# Sheet2.net
KiCad netlist of a schematic drawn in Altium Designer
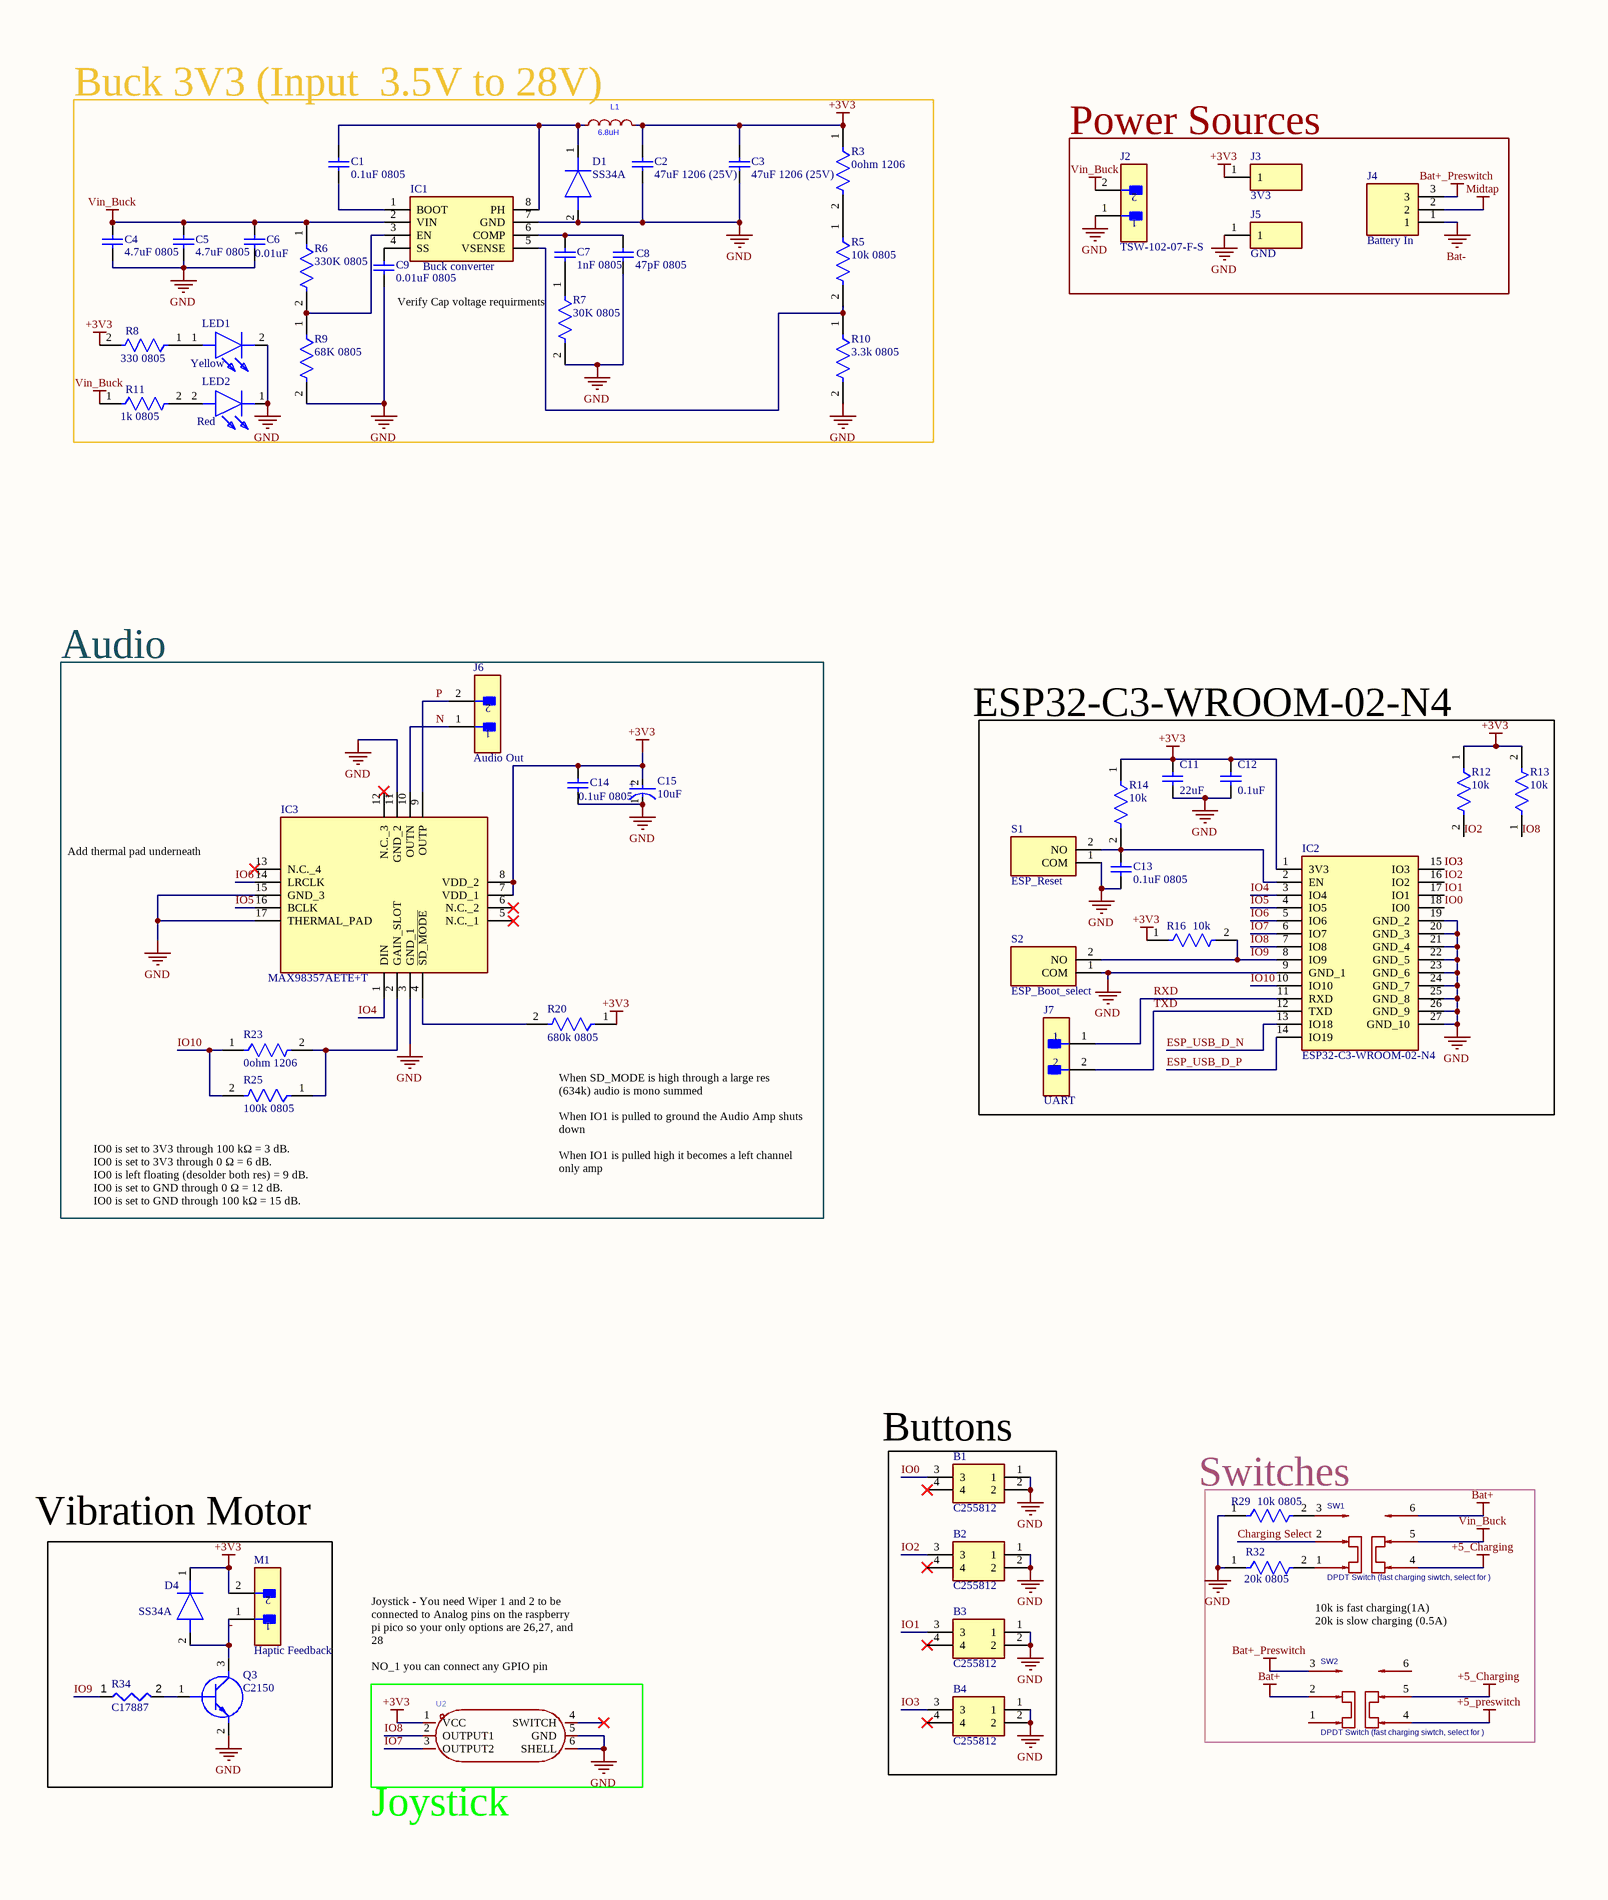
[diagram p0: Sheet2.SchDoc, left]
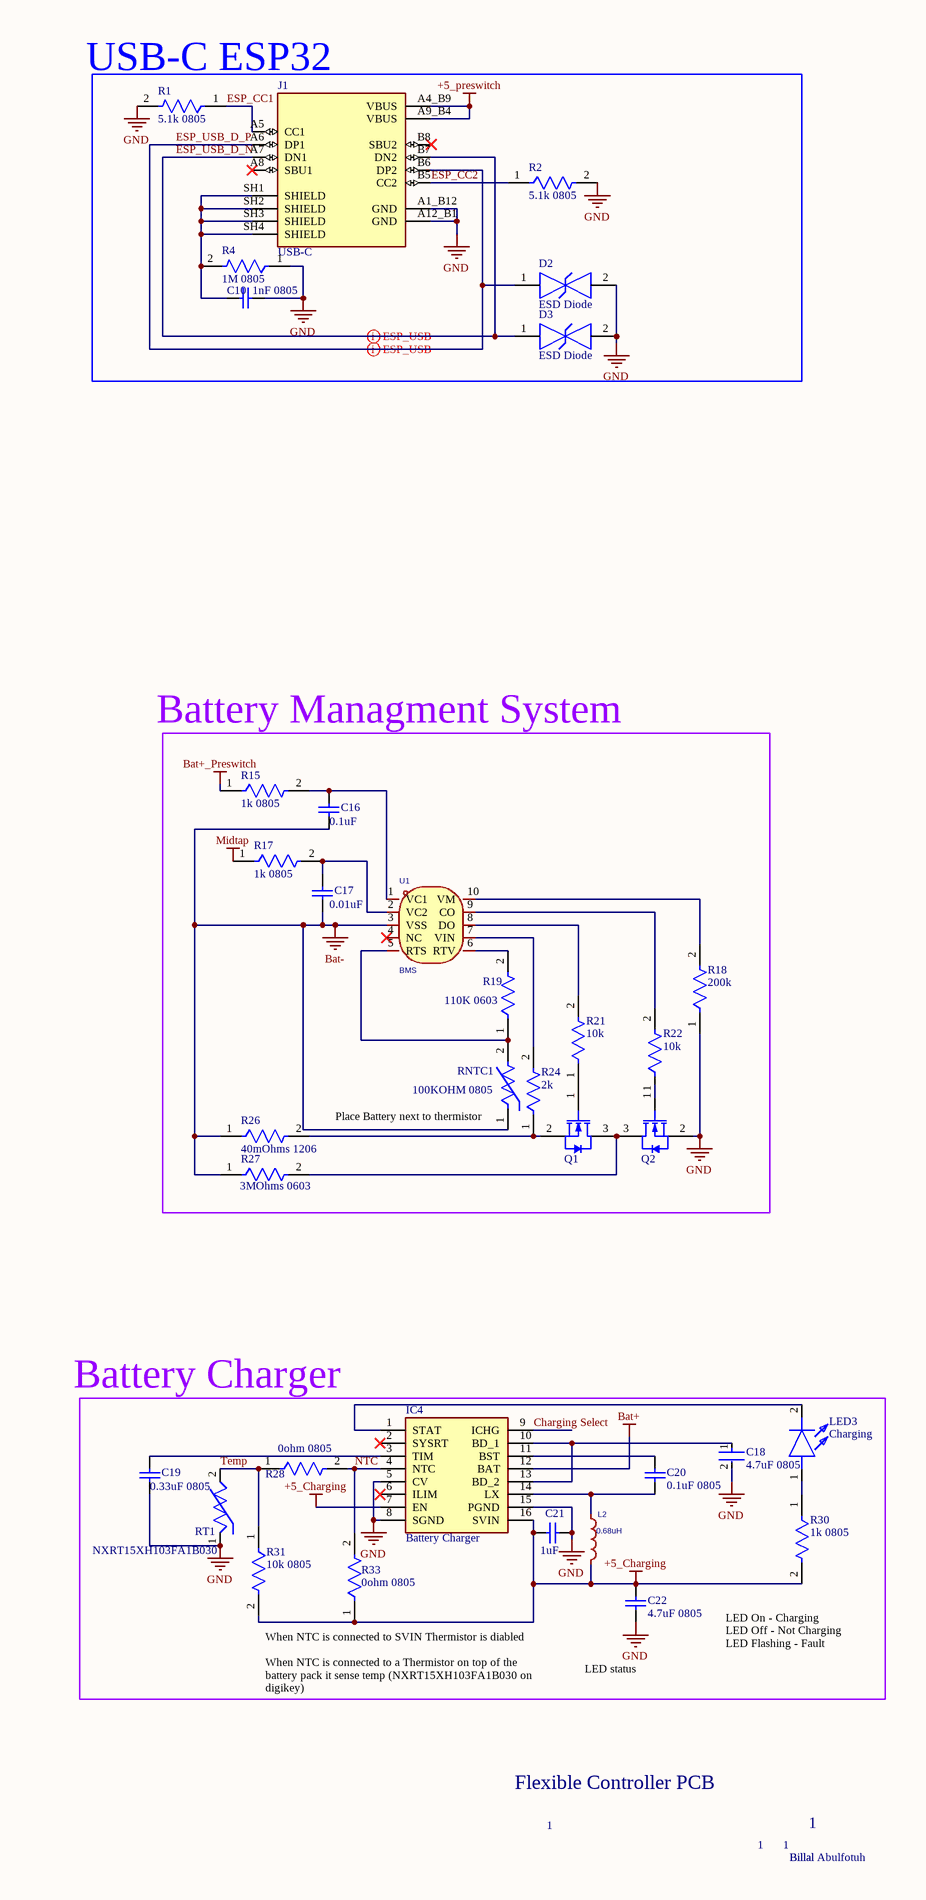
[diagram p1: Sheet2.SchDoc, right]

(export (version "E")
  (design (tool "Eeschema 10.0.6"))
  (components
    (comp (ref "B1")
      (value "C255812")
      (footprint "Button")
      (description "Switch")
      (fields (field (name "MANUFACTURER_PART_NUMBER") "1TS005F-2500-5001"))
      (libsource (lib "*") (part "1TS005F-2500-5001"))
    )
    (comp (ref "B2")
      (value "C255812")
      (footprint "Button")
      (description "Switch")
      (fields (field (name "MANUFACTURER_PART_NUMBER") "1TS005F-2500-5001"))
      (libsource (lib "*") (part "1TS005F-2500-5001"))
    )
    (comp (ref "B3")
      (value "C255812")
      (footprint "Button")
      (description "Switch")
      (fields (field (name "MANUFACTURER_PART_NUMBER") "1TS005F-2500-5001"))
      (libsource (lib "*") (part "1TS005F-2500-5001"))
    )
    (comp (ref "B4")
      (value "C255812")
      (footprint "Button")
      (description "Switch")
      (fields (field (name "MANUFACTURER_PART_NUMBER") "1TS005F-2500-5001"))
      (libsource (lib "*") (part "1TS005F-2500-5001"))
    )
    (comp (ref "C1")
      (value "0.1uF 0805")
      (footprint "CAPC2013X94X50LL20T25")
      (description "C28233")
      (fields
        (field (name "PART NUMBER") "08051C102KAT4A")
        (field (name "MANUFACTURER") "AVX Interconnect / Elco")
      )
      (libsource (lib "Altium Content Vault") (part "CAP"))
    )
    (comp (ref "C2")
      (value "47uF 1206 (25V)")
      (footprint "CAPC1206(3216)190_N")
      (description "C6119973")
      (fields (field (name "TOLERANCE") "Â±20%"))
      (libsource (lib "Altium Content Vault") (part "CAP"))
    )
    (comp (ref "C3")
      (value "47uF 1206 (25V)")
      (footprint "CAPC1206(3216)190_N")
      (description "C6119973")
      (fields (field (name "TOLERANCE") "Â±20%"))
      (libsource (lib "Altium Content Vault") (part "CAP"))
    )
    (comp (ref "C4")
      (value "4.7uF 0805")
      (footprint "CAPC2013X94X50LL20T25")
      (description "C1779")
      (fields
        (field (name "PART NUMBER") "08051C102KAT4A")
        (field (name "MANUFACTURER") "AVX Interconnect / Elco")
      )
      (libsource (lib "Altium Content Vault") (part "CAP"))
    )
    (comp (ref "C5")
      (value "4.7uF 0805")
      (footprint "CAPC2013X94X50LL20T25")
      (description "C1779")
      (fields
        (field (name "PART NUMBER") "08051C102KAT4A")
        (field (name "MANUFACTURER") "AVX Interconnect / Elco")
      )
      (libsource (lib "Altium Content Vault") (part "CAP"))
    )
    (comp (ref "C6")
      (value "0.01uF")
      (footprint "CAPC2013X94X50LL20T25")
      (description "C1710")
      (fields
        (field (name "PART NUMBER") "08051C102KAT4A")
        (field (name "MANUFACTURER") "AVX Interconnect / Elco")
      )
      (libsource (lib "Altium Content Vault") (part "CAP"))
    )
    (comp (ref "C7")
      (value "1nF 0805")
      (footprint "CAPC2013X94X50LL20T25")
      (description "C46653")
      (fields
        (field (name "PART NUMBER") "08051C102KAT4A")
        (field (name "MANUFACTURER") "AVX Interconnect / Elco")
      )
      (libsource (lib "Altium Content Vault") (part "CAP"))
    )
    (comp (ref "C8")
      (value "47pF 0805")
      (footprint "CAPC2013X94X50LL20T25")
      (description "C14857")
      (fields
        (field (name "PART NUMBER") "08051C102KAT4A")
        (field (name "MANUFACTURER") "AVX Interconnect / Elco")
      )
      (libsource (lib "Altium Content Vault") (part "CAP"))
    )
    (comp (ref "C9")
      (value "0.01uF 0805")
      (footprint "CAPC2013X94X50LL20T25")
      (description "C1710")
      (fields
        (field (name "PART NUMBER") "08051C102KAT4A")
        (field (name "MANUFACTURER") "AVX Interconnect / Elco")
      )
      (libsource (lib "Altium Content Vault") (part "CAP"))
    )
    (comp (ref "C10")
      (value "1nF 0805")
      (footprint "CAPC2013X94X50LL20T25")
      (description "C46653")
      (fields
        (field (name "PART NUMBER") "08051C102KAT4A")
        (field (name "MANUFACTURER") "AVX Interconnect / Elco")
      )
      (libsource (lib "Altium Content Vault") (part "CAP"))
    )
    (comp (ref "C11")
      (value "22uF")
      (footprint "CAPC2013X94X50LL20T25")
      (description "C45783")
      (fields
        (field (name "PART NUMBER") "08051C102KAT4A")
        (field (name "MANUFACTURER") "AVX Interconnect / Elco")
      )
      (libsource (lib "Altium Content Vault") (part "CAP"))
    )
    (comp (ref "C12")
      (value "0.1uF")
      (footprint "CAPC2013X94X50LL20T25")
      (description "C28233")
      (fields
        (field (name "PART NUMBER") "08051C102KAT4A")
        (field (name "MANUFACTURER") "AVX Interconnect / Elco")
      )
      (libsource (lib "Altium Content Vault") (part "CAP"))
    )
    (comp (ref "C13")
      (value "0.1uF 0805")
      (footprint "CAPC2013X94X50LL20T25")
      (description "C28233")
      (fields
        (field (name "PART NUMBER") "08051C102KAT4A")
        (field (name "MANUFACTURER") "AVX Interconnect / Elco")
      )
      (libsource (lib "Altium Content Vault") (part "CAP"))
    )
    (comp (ref "C14")
      (value "0.1uF 0805")
      (footprint "CAPC2013X94X50LL20T25")
      (description "C28233")
      (fields
        (field (name "PART NUMBER") "08051C102KAT4A")
        (field (name "MANUFACTURER") "AVX Interconnect / Elco")
      )
      (libsource (lib "Altium Content Vault") (part "CAP"))
    )
    (comp (ref "C15")
      (value "10uF")
      (footprint "FP-TAJA-MFG")
      (description "C7171")
      (fields (field (name "VOLTAGE") "16V") (field (name "TOLERANCE") "10%"))
      (libsource (lib "Altium Content Vault") (part "203bc49f2ac43e59fd269a8c329ed05"))
    )
    (comp (ref "C16")
      (value "0.1uF")
      (footprint "CAPC2013X94X50LL20T25")
      (description "C28233")
      (fields
        (field (name "PART NUMBER") "08051C102KAT4A")
        (field (name "MANUFACTURER") "AVX Interconnect / Elco")
      )
      (libsource (lib "Altium Content Vault") (part "CAP"))
    )
    (comp (ref "C17")
      (value "0.01uF")
      (footprint "CAPC2013X94X50LL20T25")
      (description "C1710")
      (fields
        (field (name "PART NUMBER") "08051C102KAT4A")
        (field (name "MANUFACTURER") "AVX Interconnect / Elco")
      )
      (libsource (lib "Altium Content Vault") (part "CAP"))
    )
    (comp (ref "C18")
      (value "4.7uF 0805")
      (footprint "FP-CC0805-0_85-MFG")
      (description "C1779")
      (fields (field (name "TOLERANCE") "0.1") (field (name "MANUFACTURER") "Yageo"))
      (libsource (lib "Altium Content Vault") (part "11868f565c42a9108669ba33697ecf6"))
    )
    (comp (ref "C19")
      (value "0.33uF 0805")
      (footprint "CAPC2013X94X50LL20T25")
      (description "C1740")
      (fields
        (field (name "PART NUMBER") "08051C102KAT4A")
        (field (name "MANUFACTURER") "AVX Interconnect / Elco")
      )
      (libsource (lib "Altium Content Vault") (part "CAP"))
    )
    (comp (ref "C20")
      (value "0.1uF 0805")
      (footprint "CAPC2013X94X50LL20T25")
      (description "C28233")
      (fields
        (field (name "PART NUMBER") "08051C102KAT4A")
        (field (name "MANUFACTURER") "AVX Interconnect / Elco")
      )
      (libsource (lib "Altium Content Vault") (part "CAP"))
    )
    (comp (ref "C21")
      (value "1uF")
      (footprint "CAPC2013X94X50LL20T25")
      (description "C28323")
      (fields
        (field (name "PART NUMBER") "08051C102KAT4A")
        (field (name "MANUFACTURER") "AVX Interconnect / Elco")
      )
      (libsource (lib "Altium Content Vault") (part "CAP"))
    )
    (comp (ref "C22")
      (value "4.7uF 0805")
      (footprint "CAPC2013X94X50LL20T25")
      (description "C1779")
      (fields
        (field (name "PART NUMBER") "08051C102KAT4A")
        (field (name "MANUFACTURER") "AVX Interconnect / Elco")
      )
      (libsource (lib "Altium Content Vault") (part "CAP"))
    )
    (comp (ref "D1")
      (value "SS34A")
      (footprint "SamacSys:DIOM5026X262N")
      (description "C8678")
      (libsource (lib "*") (part "SS34A"))
    )
    (comp (ref "D2")
      (value "ESD Diode")
      (footprint "FP-GG0402-MFG")
      (description "C10662")
      (fields
        (field (name "MANUFACTURER PART NUMBER") "GG040205100N2P")
        (field (name "OCTOPART") "https://octopart.com/gg040205100n2p-avx-81066081")
      )
      (libsource (lib "Altium Content Vault") (part "69d1c9d986d6c23c51904d32b7d60a2"))
    )
    (comp (ref "D3")
      (value "ESD Diode")
      (footprint "FP-GG0402-MFG")
      (description "C10662")
      (fields
        (field (name "MANUFACTURER PART NUMBER") "GG040205100N2P")
        (field (name "OCTOPART") "https://octopart.com/gg040205100n2p-avx-81066081")
      )
      (libsource (lib "Altium Content Vault") (part "69d1c9d986d6c23c51904d32b7d60a2"))
    )
    (comp (ref "D4")
      (value "SS34A")
      (footprint "SamacSys:DIOM5026X262N")
      (description "Diode")
      (libsource (lib "*") (part "SS34A"))
    )
    (comp (ref "IC1")
      (value "Buck converter")
      (footprint "SamacSys:SOIC127P600X175-8N")
      (description "C9865")
      (fields
        (field (name "MANUFACTURER_PART_NUMBER") "TPS54331D")
        (field (name "MOUSER PART NUMBER") "595-TPS54331D")
      )
      (libsource (lib "*") (part "TPS54331D"))
    )
    (comp (ref "IC2")
      (value "ESP32-C3-WROOM-02-N4")
      (footprint "SamacSys:ESP32C3WROOM02N4")
      (description "C2934560")
      (fields (field (name "MOUSER PART NUMBER") "356-ESP32C3WROOM02N4"))
      (libsource (lib "*") (part "ESP32-C3-WROOM-02-N4"))
    )
    (comp (ref "IC3")
      (value "MAX98357AETE+T")
      (footprint "SamacSys:QFN50P300X300X80-17N")
      (description "C910544")
      (fields (field (name "MOUSER PART NUMBER") "700-MAX98357AETE+T"))
      (libsource (lib "*") (part "MAX98357AETE+T"))
    )
    (comp (ref "IC4")
      (value "Battery Charger")
      (footprint "SamacSys:SY6982CQDC")
      (description "C7435940")
      (fields (field (name "MANUFACTURER_PART_NUMBER") "SY6982CQDC"))
      (libsource (lib "*") (part "SY6982CQDC"))
    )
    (comp (ref "J1")
      (value "USB-C")
      (footprint "KINGHELM_KH-TYPE-C-16P")
      (description "C2765186")
      (fields (field (name "MF") "kinghelm") (field (name "MP") "KH-TYPE-C-16P"))
      (libsource (lib "Schlib1") (part "KH-TYPE-C-16P"))
    )
    (comp (ref "J2")
      (value "TSW-102-07-F-S")
      (footprint "FP-TSW-102-07-F-S-MFG")
      (description "CONN HEADER VERT 2POS 2.54MM")
      (libsource (lib "Altium Content Vault") (part "3bc925449376181038e59eaffc5286c"))
    )
    (comp (ref "J3")
      (value "3V3")
      (footprint "SamacSys:HDRV1W66P0X254_1X1_213X254X1074P")
      (description "Connector")
      (fields
        (field (name "MANUFACTURER_PART_NUMBER") "87224-1")
        (field (name "MOUSER PART NUMBER") "571-872241")
      )
      (libsource (lib "*") (part "87224-1"))
    )
    (comp (ref "J4")
      (value "Battery In")
      (footprint "SamacSys:B3BXHALFSN")
      (description "C144394")
      (fields
        (field (name "MANUFACTURER_PART_NUMBER") "B3B-XH-A(LF)(SN)")
        (field (name "MOUSER PART NUMBER") "306-B3BXHALFSNP")
      )
      (libsource (lib "*") (part "B3B-XH-A_LF__SN_"))
    )
    (comp (ref "J5")
      (value "GND")
      (footprint "SamacSys:HDRV1W66P0X254_1X1_213X254X1074P")
      (description "Connector")
      (fields
        (field (name "MANUFACTURER_PART_NUMBER") "87224-1")
        (field (name "MOUSER PART NUMBER") "571-872241")
      )
      (libsource (lib "*") (part "87224-1"))
    )
    (comp (ref "J6")
      (value "Audio Out")
      (footprint "FP-TSW-102-07-F-S-MFG")
      (description "CONN HEADER VERT 2POS 2.54MM")
      (libsource (lib "Altium Content Vault") (part "3bc925449376181038e59eaffc5286c"))
    )
    (comp (ref "J7")
      (value "UART")
      (footprint "FP-TSW-102-07-F-S-MFG")
      (description "CONN HEADER VERT 2POS 2.54MM")
      (libsource (lib "") (part "3bc925449376181038e59eaffc5286c_1"))
    )
    (comp (ref "L1")
      (value "6.8uH")
      (footprint "IND-SMD_L7.0-W6.6")
      (description "C167221")
      (fields (field (name "MANUFACTURER") "cjiang(长江微电)") (field (name "MANUFACTURER PART") "FXL0630-6R8-M"))
      (libsource (lib "Schlib1") (part "FXL0630-6R8-M"))
    )
    (comp (ref "L2")
      (value "0.68uH")
      (footprint "IND-SMD_L2.5-W2.0")
      (description "C492726")
      (fields
        (field (name "MANUFACTURER") "Sumida(胜美达)")
        (field (name "MANUFACTURER PART") "252012CDMCDDS-R68MC")
      )
      (libsource (lib "Schlib1") (part "252012CDMCDDS-R68MC"))
    )
    (comp (ref "LED1")
      (value "Yellow")
      (footprint "SamacSys:KT0805G")
      (description "C2296")
      (fields (field (name "MANUFACTURER_PART_NUMBER") "KT-0805G"))
      (libsource (lib "*") (part "KT-0805G"))
    )
    (comp (ref "LED2")
      (value "Red")
      (footprint "SamacSys:LEDC1608X70N")
      (description "C2286")
      (fields (field (name "MANUFACTURER_PART_NUMBER") "KT-0603R"))
      (libsource (lib "*") (part "KT-0603R"))
    )
    (comp (ref "LED3")
      (value "Charging")
      (footprint "SamacSys:KT0805G")
      (description "C2297")
      (fields (field (name "MANUFACTURER_PART_NUMBER") "KT-0805G"))
      (libsource (lib "*") (part "KT-0805G"))
    )
    (comp (ref "M1")
      (value "Haptic Feedback")
      (footprint "FP-TSW-102-07-F-S-MFG")
      (description "CONN HEADER VERT 2POS 2.54MM")
      (libsource (lib "Altium Content Vault") (part "3bc925449376181038e59eaffc5286c"))
    )
    (comp (ref "Q1")
      (value "Discharge Protection")
      (footprint "ONSC-SOT-23-3-318-08_V")
      (description "C20917")
      (fields (field (name "MANUFACTURER") "On Semiconductor") (field (name "PARTNUMBER") "2N7002LT1G"))
      (libsource (lib "Altium Content Vault") (part "ONSC-NMOS-G1S2D3-3"))
    )
    (comp (ref "Q2")
      (value "Charge Protection")
      (footprint "ONSC-SOT-23-3-318-08_V")
      (description "C20917")
      (fields (field (name "MANUFACTURER") "On Semiconductor") (field (name "PARTNUMBER") "2N7002LT1G"))
      (libsource (lib "Altium Content Vault") (part "ONSC-NMOS-G1S2D3-3"))
    )
    (comp (ref "Q3")
      (value "C2150")
      (footprint "SamacSys:SOT95P240X115-3N")
      (fields
        (field (name "MANUFACTURER_PART_NUMBER") "SS8050-G")
        (field (name "MOUSER PART NUMBER") "750-SS8050-G")
      )
      (libsource (lib "*") (part "SS8050-G"))
    )
    (comp (ref "R1")
      (value "5.1k 0805")
      (footprint "FP-RN73R2A-IPC_C")
      (description "C27834")
      (libsource (lib "Altium Content Vault") (part "1029c3af85768c4190bb7ad29bc67b5"))
    )
    (comp (ref "R2")
      (value "5.1k 0805")
      (footprint "FP-RN73R2A-IPC_C")
      (description "C27834")
      (libsource (lib "Altium Content Vault") (part "1029c3af85768c4190bb7ad29bc67b5"))
    )
    (comp (ref "R3")
      (value "0ohm 1206")
      (footprint "FP-HCJ1206-MFG")
      (description "C17888")
      (libsource (lib "Altium Content Vault") (part "1029c3af85768c4190bb7ad29bc67b5"))
    )
    (comp (ref "R4")
      (value "1M 0805")
      (footprint "FP-RN73R2A-IPC_C")
      (description "C17514")
      (libsource (lib "Altium Content Vault") (part "1029c3af85768c4190bb7ad29bc67b5"))
    )
    (comp (ref "R5")
      (value "10k 0805")
      (footprint "FP-RN73R2A-IPC_C")
      (description "C17414")
      (libsource (lib "Altium Content Vault") (part "1029c3af85768c4190bb7ad29bc67b5"))
    )
    (comp (ref "R6")
      (value "330K 0805")
      (footprint "FP-RN73R2A-IPC_C")
      (description "C17629")
      (libsource (lib "Altium Content Vault") (part "1029c3af85768c4190bb7ad29bc67b5"))
    )
    (comp (ref "R7")
      (value "30K 0805")
      (footprint "FP-RN73R2A-IPC_C")
      (description "C17621")
      (libsource (lib "Altium Content Vault") (part "1029c3af85768c4190bb7ad29bc67b5"))
    )
    (comp (ref "R8")
      (value "330 0805")
      (footprint "FP-RN73R2A-IPC_C")
      (description "C17630")
      (libsource (lib "Altium Content Vault") (part "1029c3af85768c4190bb7ad29bc67b5"))
    )
    (comp (ref "R9")
      (value "68K 0805")
      (footprint "FP-RN73R2A-IPC_C")
      (description "C17801")
      (libsource (lib "Altium Content Vault") (part "1029c3af85768c4190bb7ad29bc67b5"))
    )
    (comp (ref "R10")
      (value "3.3k 0805")
      (footprint "FP-RN73R2A-IPC_C")
      (description "C26010")
      (libsource (lib "Altium Content Vault") (part "1029c3af85768c4190bb7ad29bc67b5"))
    )
    (comp (ref "R11")
      (value "1k 0805")
      (footprint "FP-RN73R2A-IPC_C")
      (description "C1015")
      (libsource (lib "Altium Content Vault") (part "1029c3af85768c4190bb7ad29bc67b5"))
    )
    (comp (ref "R12")
      (value "10k")
      (footprint "FP-RN73R2A-IPC_C")
      (description "C17414")
      (libsource (lib "Altium Content Vault") (part "1029c3af85768c4190bb7ad29bc67b5"))
    )
    (comp (ref "R13")
      (value "10k")
      (footprint "FP-RN73R2A-IPC_C")
      (description "C17414")
      (libsource (lib "Altium Content Vault") (part "1029c3af85768c4190bb7ad29bc67b5"))
    )
    (comp (ref "R14")
      (value "10k")
      (footprint "FP-RN73R2A-IPC_C")
      (description "C17414")
      (libsource (lib "Altium Content Vault") (part "1029c3af85768c4190bb7ad29bc67b5"))
    )
    (comp (ref "R15")
      (value "1k 0805")
      (footprint "FP-RN73R2A-IPC_C")
      (description "C1015")
      (libsource (lib "Altium Content Vault") (part "1029c3af85768c4190bb7ad29bc67b5"))
    )
    (comp (ref "R16")
      (value "10k")
      (footprint "FP-RN73R2A-IPC_C")
      (description "C17414")
      (libsource (lib "Altium Content Vault") (part "1029c3af85768c4190bb7ad29bc67b5"))
    )
    (comp (ref "R17")
      (value "1k 0805")
      (footprint "FP-RN73R2A-IPC_C")
      (description "C1015")
      (libsource (lib "Altium Content Vault") (part "1029c3af85768c4190bb7ad29bc67b5"))
    )
    (comp (ref "R18")
      (value "200k")
      (footprint "FP-RN73R2A-IPC_C")
      (description "C17539")
      (libsource (lib "Altium Content Vault") (part "1029c3af85768c4190bb7ad29bc67b5"))
    )
    (comp (ref "R19")
      (value "110K 0603")
      (footprint "FP-RMCF0603-IPC_C")
      (description "C25805")
      (fields (field (name "TOLERANCE") "5%"))
      (libsource (lib "Altium Content Vault") (part "1029c3af85768c4190bb7ad29bc67b5"))
    )
    (comp (ref "R20")
      (value "680k 0805")
      (footprint "FP-RN73R2A-IPC_C")
      (description "C17797")
      (libsource (lib "Altium Content Vault") (part "1029c3af85768c4190bb7ad29bc67b5"))
    )
    (comp (ref "R21")
      (value "10k")
      (footprint "FP-RN73R2A-IPC_C")
      (description "C17414")
      (libsource (lib "Altium Content Vault") (part "1029c3af85768c4190bb7ad29bc67b5"))
    )
    (comp (ref "R22")
      (value "10k")
      (footprint "FP-RN73R2A-IPC_C")
      (description "C17414")
      (libsource (lib "Altium Content Vault") (part "1029c3af85768c4190bb7ad29bc67b5"))
    )
    (comp (ref "R23")
      (value "0ohm 1206")
      (footprint "FP-HCJ1206-MFG")
      (description "C17888")
      (libsource (lib "Altium Content Vault") (part "1029c3af85768c4190bb7ad29bc67b5"))
    )
    (comp (ref "R24")
      (value "2k")
      (footprint "FP-RN73R2A-IPC_C")
      (description "C17604")
      (libsource (lib "Altium Content Vault") (part "1029c3af85768c4190bb7ad29bc67b5"))
    )
    (comp (ref "R25")
      (value "100k 0805")
      (footprint "FP-RN73R2A-IPC_C")
      (description "C149504")
      (libsource (lib "Altium Content Vault") (part "1029c3af85768c4190bb7ad29bc67b5"))
    )
    (comp (ref "R26")
      (value "40mOhms 1206")
      (footprint "FP-WSL1206-0_508-MFG")
      (description "C49654479")
      (fields (field (name "TOLERANCE") "1%"))
      (libsource (lib "Altium Content Vault") (part "1029c3af85768c4190bb7ad29bc67b5"))
    )
    (comp (ref "R27")
      (value "3MOhms 0603")
      (footprint "FP-AC0603-MFG")
      (description "RES 3MΩ 1.00% 0.1W 0603")
      (fields (field (name "TOLERANCE") "1%"))
      (libsource (lib "Altium Content Vault") (part "1029c3af85768c4190bb7ad29bc67b5"))
    )
    (comp (ref "R28")
      (value "0ohm 0805")
      (footprint "FP-HCJ0805-MFG")
      (description "C17477")
      (libsource (lib "Altium Content Vault") (part "1029c3af85768c4190bb7ad29bc67b5"))
    )
    (comp (ref "R29")
      (value "10k 0805")
      (footprint "FP-RN73R2A-IPC_C")
      (description "C17414")
      (libsource (lib "Altium Content Vault") (part "1029c3af85768c4190bb7ad29bc67b5"))
    )
    (comp (ref "R30")
      (value "1k 0805")
      (footprint "FP-RN73R2A-IPC_C")
      (description "C1015")
      (libsource (lib "Altium Content Vault") (part "1029c3af85768c4190bb7ad29bc67b5"))
    )
    (comp (ref "R31")
      (value "10k 0805")
      (footprint "FP-RN73R2A-IPC_C")
      (description "C17414")
      (libsource (lib "Altium Content Vault") (part "1029c3af85768c4190bb7ad29bc67b5"))
    )
    (comp (ref "R32")
      (value "20k 0805")
      (footprint "FP-RN73R2A-IPC_C")
      (description "C4328")
      (libsource (lib "Altium Content Vault") (part "1029c3af85768c4190bb7ad29bc67b5"))
    )
    (comp (ref "R33")
      (value "0ohm 0805")
      (footprint "FP-HCJ0805-MFG")
      (description "C17477")
      (libsource (lib "Altium Content Vault") (part "1029c3af85768c4190bb7ad29bc67b5"))
    )
    (comp (ref "R34")
      (value "C17887")
      (footprint "Resistor 300Ohms")
      (libsource (lib "Schlib1") (part "Resistor 300Ohms"))
    )
    (comp (ref "RNTC1")
      (value "100KOHM 0805")
      (footprint "FP-NCP21-0_2-IPC_A")
      (description "C338605")
      (fields (field (name "TOLERANCE") "5%"))
      (libsource (lib "Altium Content Vault") (part "3b148a6ebabc5fb4d708a66c052d352"))
    )
    (comp (ref "RT1")
      (value "NXRT15XH103FA1B030")
      (footprint "PcbLib1:THERM_NXRT15XH103FA1B030")
      (description "THERMISTOR NTC 10KOHM 3380K BEAD")
      (fields (field (name "MF") "Murata"))
      (libsource (lib "Schlib1") (part "NXRT15XH103FA1B030"))
    )
    (comp (ref "S1")
      (value "ESP_Reset")
      (footprint "SamacSys:TS1088AR02016")
      (description "C720477")
      (fields (field (name "MANUFACTURER_PART_NUMBER") "TS-1088-AR02016"))
      (libsource (lib "*") (part "TS-1088-AR02016"))
    )
    (comp (ref "S2")
      (value "ESP_Boot_select")
      (footprint "SamacSys:TS1088AR02016")
      (description "C720477")
      (fields (field (name "MANUFACTURER_PART_NUMBER") "TS-1088-AR02016"))
      (libsource (lib "*") (part "TS-1088-AR02016"))
    )
    (comp (ref "SW1")
      (value "DPDT Switch (fast charging siwtch, select for )")
      (footprint "PCBComponent_1 - duplicate")
      (description "C2848931")
      (fields (field (name "MANUFACTURER") "G-Switch(品赞)") (field (name "MANUFACTURER PART") "SS-22F32-G060"))
      (libsource (lib "Schlib1") (part "SS-22F32-G060"))
    )
    (comp (ref "SW2")
      (value "DPDT Switch (fast charging siwtch, select for )")
      (footprint "PCBComponent_1 - duplicate")
      (description "C2848931")
      (fields (field (name "MANUFACTURER") "G-Switch(品赞)") (field (name "MANUFACTURER PART") "SS-22F32-G060"))
      (libsource (lib "Schlib1") (part "SS-22F32-G060"))
    )
    (comp (ref "U1")
      (value "BMS")
      (footprint "MSOP-10_L3.0-W3.0-P0.50-LS4.9-BL - duplicate")
      (description "C22446437")
      (fields (field (name "MANUFACTURER") "iCM(创芯微)") (field (name "MANUFACTURER PART") "CM1022-CA"))
      (libsource (lib "Schlib1") (part "CM1022-CA"))
    )
    (comp (ref "U2")
      (value "C42411044")
      (footprint "Correct Joystick")
      (fields
        (field (name "MANUFACTURER") "YTL(亚特联)")
        (field (name "MANUFACTURER PART") "YHE-YG16-001 SH1B166A1")
      )
      (libsource (lib "altium-import") (part "root_0_YHE-YG16-001 SH1B166A1_"))
    )
  )
  (nets
    (net (code "1") (name "+3V3") (class "Default")
      (node (ref "C11") (pin "1") (pinfunction "1_1") (pintype "passive"))
      (node (ref "C12") (pin "1") (pinfunction "1_1") (pintype "passive"))
      (node (ref "C14") (pin "1") (pinfunction "1_1") (pintype "passive"))
      (node (ref "C15") (pin "2") (pinfunction "A_2") (pintype "passive"))
      (node (ref "C2") (pin "2") (pinfunction "2_2") (pintype "passive"))
      (node (ref "C3") (pin "2") (pinfunction "2_2") (pintype "passive"))
      (node (ref "D4") (pin "1") (pinfunction "K_1") (pintype "passive"))
      (node (ref "IC2") (pin "1") (pinfunction "3V3_1") (pintype "passive"))
      (node (ref "IC3") (pin "7") (pinfunction "VDD_1_7") (pintype "passive"))
      (node (ref "IC3") (pin "8") (pinfunction "VDD_2_8") (pintype "passive"))
      (node (ref "J3") (pin "1") (pinfunction "1_1") (pintype "passive"))
      (node (ref "L1") (pin "2") (pinfunction "2_2") (pintype "passive"))
      (node (ref "M1") (pin "2") (pinfunction "2_2") (pintype "passive"))
      (node (ref "R12") (pin "1") (pinfunction "1_1") (pintype "passive"))
      (node (ref "R13") (pin "2") (pinfunction "2_2") (pintype "passive"))
      (node (ref "R14") (pin "1") (pinfunction "1_1") (pintype "passive"))
      (node (ref "R16") (pin "1") (pinfunction "1_1") (pintype "passive"))
      (node (ref "R20") (pin "1") (pinfunction "1_1") (pintype "passive"))
      (node (ref "R3") (pin "1") (pinfunction "1_1") (pintype "passive"))
      (node (ref "R8") (pin "2") (pinfunction "2_2") (pintype "passive"))
      (node (ref "U2") (pin "1") (pinfunction "VCC_1") (pintype "passive"))
    )
    (net (code "2") (name "+5_Charging") (class "Default")
      (node (ref "C21") (pin "1") (pinfunction "1_1") (pintype "passive"))
      (node (ref "C22") (pin "1") (pinfunction "1_1") (pintype "passive"))
      (node (ref "IC4") (pin "16") (pinfunction "SVIN_16") (pintype "passive"))
      (node (ref "IC4") (pin "7") (pinfunction "EN_7") (pintype "passive"))
      (node (ref "L2") (pin "2") (pinfunction "2_2") (pintype "passive"))
      (node (ref "R30") (pin "2") (pinfunction "2_2") (pintype "passive"))
      (node (ref "R31") (pin "2") (pinfunction "2_2") (pintype "passive"))
      (node (ref "R33") (pin "1") (pinfunction "1_1") (pintype "passive"))
      (node (ref "SW1") (pin "4") (pinfunction "4_4") (pintype "passive"))
      (node (ref "SW2") (pin "5") (pinfunction "5_5") (pintype "passive"))
    )
    (net (code "3") (name "+5_preswitch") (class "Default")
      (node (ref "J1") (pin "A4_B9") (pinfunction "VBUS_A4_B9") (pintype "power_in"))
      (node (ref "J1") (pin "A9_B4") (pinfunction "VBUS_A9_B4") (pintype "power_in"))
      (node (ref "SW2") (pin "4") (pinfunction "4_4") (pintype "passive"))
    )
    (net (code "4") (name "/-") (class "Default")
      (node (ref "D4") (pin "2") (pinfunction "A_2") (pintype "passive"))
      (node (ref "M1") (pin "1") (pinfunction "1_1") (pintype "passive"))
      (node (ref "Q3") (pin "3") (pinfunction "C_3") (pintype "passive"))
    )
    (net (code "5") (name "/Charging Select") (class "Default")
      (node (ref "IC4") (pin "9") (pinfunction "ICHG_9") (pintype "passive"))
      (node (ref "SW1") (pin "2") (pinfunction "2_2") (pintype "passive"))
    )
    (net (code "6") (name "/ESP_CC1") (class "Default")
      (node (ref "J1") (pin "A5") (pinfunction "CC1_A5") (pintype "bidirectional"))
      (node (ref "R1") (pin "1") (pinfunction "1_1") (pintype "passive"))
    )
    (net (code "7") (name "/ESP_CC2") (class "Default")
      (node (ref "J1") (pin "B5") (pinfunction "CC2_B5") (pintype "bidirectional"))
      (node (ref "R2") (pin "1") (pinfunction "1_1") (pintype "passive"))
    )
    (net (code "8") (name "/ESP_USB_D_N") (class "Default")
      (node (ref "D3") (pin "1") (pinfunction "IO_1_1") (pintype "passive"))
      (node (ref "IC2") (pin "13") (pinfunction "IO18_13") (pintype "passive"))
      (node (ref "J1") (pin "A7") (pinfunction "DN1_A7") (pintype "bidirectional"))
      (node (ref "J1") (pin "B7") (pinfunction "DN2_B7") (pintype "bidirectional"))
    )
    (net (code "9") (name "/ESP_USB_D_P") (class "Default")
      (node (ref "D2") (pin "1") (pinfunction "IO_1_1") (pintype "passive"))
      (node (ref "IC2") (pin "14") (pinfunction "IO19_14") (pintype "passive"))
      (node (ref "J1") (pin "A6") (pinfunction "DP1_A6") (pintype "bidirectional"))
      (node (ref "J1") (pin "B6") (pinfunction "DP2_B6") (pintype "bidirectional"))
    )
    (net (code "10") (name "/IO0") (class "Default")
      (node (ref "B1") (pin "3") (pinfunction "3_3") (pintype "passive"))
      (node (ref "IC2") (pin "18") (pinfunction "IO0_18") (pintype "passive"))
    )
    (net (code "11") (name "/IO1") (class "Default")
      (node (ref "B3") (pin "3") (pinfunction "3_3") (pintype "passive"))
      (node (ref "IC2") (pin "17") (pinfunction "IO1_17") (pintype "passive"))
    )
    (net (code "12") (name "/IO2") (class "Default")
      (node (ref "B2") (pin "3") (pinfunction "3_3") (pintype "passive"))
      (node (ref "IC2") (pin "16") (pinfunction "IO2_16") (pintype "passive"))
      (node (ref "R12") (pin "2") (pinfunction "2_2") (pintype "passive"))
    )
    (net (code "13") (name "/IO3") (class "Default")
      (node (ref "B4") (pin "3") (pinfunction "3_3") (pintype "passive"))
      (node (ref "IC2") (pin "15") (pinfunction "IO3_15") (pintype "passive"))
    )
    (net (code "14") (name "/IO4") (class "Default")
      (node (ref "IC2") (pin "3") (pinfunction "IO4_3") (pintype "passive"))
      (node (ref "IC3") (pin "1") (pinfunction "DIN_1") (pintype "passive"))
    )
    (net (code "15") (name "/IO5") (class "Default")
      (node (ref "IC2") (pin "4") (pinfunction "IO5_4") (pintype "passive"))
      (node (ref "IC3") (pin "16") (pinfunction "BCLK_16") (pintype "passive"))
    )
    (net (code "16") (name "/IO6") (class "Default")
      (node (ref "IC2") (pin "5") (pinfunction "IO6_5") (pintype "passive"))
      (node (ref "IC3") (pin "14") (pinfunction "LRCLK_14") (pintype "passive"))
    )
    (net (code "17") (name "/IO7") (class "Default")
      (node (ref "IC2") (pin "6") (pinfunction "IO7_6") (pintype "passive"))
      (node (ref "U2") (pin "3") (pinfunction "OUTPUT2_3") (pintype "passive"))
    )
    (net (code "18") (name "/IO8") (class "Default")
      (node (ref "IC2") (pin "7") (pinfunction "IO8_7") (pintype "passive"))
      (node (ref "R13") (pin "1") (pinfunction "1_1") (pintype "passive"))
      (node (ref "U2") (pin "2") (pinfunction "OUTPUT1_2") (pintype "passive"))
    )
    (net (code "19") (name "/IO9") (class "Default")
      (node (ref "IC2") (pin "8") (pinfunction "IO9_8") (pintype "passive"))
      (node (ref "R16") (pin "2") (pinfunction "2_2") (pintype "passive"))
      (node (ref "R34") (pin "1") (pinfunction "1_1") (pintype "passive"))
      (node (ref "S2") (pin "2") (pinfunction "NO_2") (pintype "passive"))
    )
    (net (code "20") (name "/IO10") (class "Default")
      (node (ref "IC2") (pin "10") (pinfunction "IO10_10") (pintype "passive"))
      (node (ref "R23") (pin "1") (pinfunction "1_1") (pintype "passive"))
      (node (ref "R25") (pin "2") (pinfunction "2_2") (pintype "passive"))
    )
    (net (code "21") (name "/N") (class "Default")
      (node (ref "IC3") (pin "10") (pinfunction "OUTN_10") (pintype "passive"))
      (node (ref "J6") (pin "1") (pinfunction "1_1") (pintype "passive"))
    )
    (net (code "22") (name "/NTC") (class "Default")
      (node (ref "IC4") (pin "4") (pinfunction "NTC_4") (pintype "passive"))
      (node (ref "R28") (pin "2") (pinfunction "2_2") (pintype "passive"))
      (node (ref "R33") (pin "2") (pinfunction "2_2") (pintype "passive"))
    )
    (net (code "23") (name "/P") (class "Default")
      (node (ref "IC3") (pin "9") (pinfunction "OUTP_9") (pintype "passive"))
      (node (ref "J6") (pin "2") (pinfunction "2_2") (pintype "passive"))
    )
    (net (code "24") (name "/RXD") (class "Default")
      (node (ref "IC2") (pin "11") (pinfunction "RXD_11") (pintype "passive"))
      (node (ref "J7") (pin "1") (pinfunction "1_1") (pintype "passive"))
    )
    (net (code "25") (name "/TXD") (class "Default")
      (node (ref "IC2") (pin "12") (pinfunction "TXD_12") (pintype "passive"))
      (node (ref "J7") (pin "2") (pinfunction "2_2") (pintype "passive"))
    )
    (net (code "26") (name "/Temp") (class "Default")
      (node (ref "R28") (pin "1") (pinfunction "1_1") (pintype "passive"))
      (node (ref "R31") (pin "1") (pinfunction "1_1") (pintype "passive"))
      (node (ref "RT1") (pin "2") (pinfunction "2_2") (pintype "passive"))
    )
    (net (code "27") (name "Bat+") (class "Default")
      (node (ref "IC4") (pin "12") (pinfunction "BAT_12") (pintype "passive"))
      (node (ref "SW1") (pin "6") (pinfunction "6_6") (pintype "passive"))
      (node (ref "SW2") (pin "2") (pinfunction "2_2") (pintype "passive"))
    )
    (net (code "28") (name "Bat+_Preswitch") (class "Default")
      (node (ref "J4") (pin "3") (pinfunction "3_3") (pintype "passive"))
      (node (ref "R15") (pin "1") (pinfunction "1_1") (pintype "passive"))
      (node (ref "SW2") (pin "3") (pinfunction "3_3") (pintype "passive"))
    )
    (net (code "29") (name "Bat-") (class "Default")
      (node (ref "C16") (pin "2") (pinfunction "2_2") (pintype "passive"))
      (node (ref "C17") (pin "2") (pinfunction "2_2") (pintype "passive"))
      (node (ref "J4") (pin "1") (pinfunction "1_1") (pintype "passive"))
      (node (ref "R26") (pin "1") (pinfunction "1_1") (pintype "passive"))
      (node (ref "R27") (pin "1") (pinfunction "1_1") (pintype "passive"))
      (node (ref "RNTC1") (pin "1") (pinfunction "1_1") (pintype "passive"))
      (node (ref "U1") (pin "3") (pinfunction "VSS_3") (pintype "passive"))
    )
    (net (code "30") (name "GND") (class "Default")
      (node (ref "B1") (pin "1") (pinfunction "1_1") (pintype "passive"))
      (node (ref "B1") (pin "2") (pinfunction "2_2") (pintype "passive"))
      (node (ref "B2") (pin "1") (pinfunction "1_1") (pintype "passive"))
      (node (ref "B2") (pin "2") (pinfunction "2_2") (pintype "passive"))
      (node (ref "B3") (pin "1") (pinfunction "1_1") (pintype "passive"))
      (node (ref "B3") (pin "2") (pinfunction "2_2") (pintype "passive"))
      (node (ref "B4") (pin "1") (pinfunction "1_1") (pintype "passive"))
      (node (ref "B4") (pin "2") (pinfunction "2_2") (pintype "passive"))
      (node (ref "C10") (pin "1") (pinfunction "1_1") (pintype "passive"))
      (node (ref "C11") (pin "2") (pinfunction "2_2") (pintype "passive"))
      (node (ref "C12") (pin "2") (pinfunction "2_2") (pintype "passive"))
      (node (ref "C13") (pin "2") (pinfunction "2_2") (pintype "passive"))
      (node (ref "C14") (pin "2") (pinfunction "2_2") (pintype "passive"))
      (node (ref "C15") (pin "1") (pinfunction "C_1") (pintype "passive"))
      (node (ref "C18") (pin "2") (pinfunction "2_2") (pintype "passive"))
      (node (ref "C19") (pin "2") (pinfunction "2_2") (pintype "passive"))
      (node (ref "C2") (pin "1") (pinfunction "1_1") (pintype "passive"))
      (node (ref "C21") (pin "2") (pinfunction "2_2") (pintype "passive"))
      (node (ref "C22") (pin "2") (pinfunction "2_2") (pintype "passive"))
      (node (ref "C3") (pin "1") (pinfunction "1_1") (pintype "passive"))
      (node (ref "C4") (pin "2") (pinfunction "2_2") (pintype "passive"))
      (node (ref "C5") (pin "2") (pinfunction "2_2") (pintype "passive"))
      (node (ref "C6") (pin "2") (pinfunction "2_2") (pintype "passive"))
      (node (ref "C8") (pin "2") (pinfunction "2_2") (pintype "passive"))
      (node (ref "C9") (pin "2") (pinfunction "2_2") (pintype "passive"))
      (node (ref "D1") (pin "2") (pinfunction "A_2") (pintype "passive"))
      (node (ref "D2") (pin "2") (pinfunction "IO_2_2") (pintype "passive"))
      (node (ref "D3") (pin "2") (pinfunction "IO_2_2") (pintype "passive"))
      (node (ref "IC1") (pin "7") (pinfunction "GND_7") (pintype "passive"))
      (node (ref "IC2") (pin "19") (pinfunction "GND_2_19") (pintype "passive"))
      (node (ref "IC2") (pin "20") (pinfunction "GND_3_20") (pintype "passive"))
      (node (ref "IC2") (pin "21") (pinfunction "GND_4_21") (pintype "passive"))
      (node (ref "IC2") (pin "22") (pinfunction "GND_5_22") (pintype "passive"))
      (node (ref "IC2") (pin "23") (pinfunction "GND_6_23") (pintype "passive"))
      (node (ref "IC2") (pin "24") (pinfunction "GND_7_24") (pintype "passive"))
      (node (ref "IC2") (pin "25") (pinfunction "GND_8_25") (pintype "passive"))
      (node (ref "IC2") (pin "26") (pinfunction "GND_9_26") (pintype "passive"))
      (node (ref "IC2") (pin "27") (pinfunction "GND_10_27") (pintype "passive"))
      (node (ref "IC2") (pin "9") (pinfunction "GND_1_9") (pintype "passive"))
      (node (ref "IC3") (pin "11") (pinfunction "GND_2_11") (pintype "passive"))
      (node (ref "IC3") (pin "15") (pinfunction "GND_3_15") (pintype "passive"))
      (node (ref "IC3") (pin "17") (pinfunction "THERMAL_PAD_17") (pintype "passive"))
      (node (ref "IC3") (pin "3") (pinfunction "GND_1_3") (pintype "passive"))
      (node (ref "IC4") (pin "15") (pinfunction "PGND_15") (pintype "passive"))
      (node (ref "IC4") (pin "5") (pinfunction "CV_5") (pintype "passive"))
      (node (ref "IC4") (pin "8") (pinfunction "SGND_8") (pintype "passive"))
      (node (ref "J1") (pin "A12_B1") (pinfunction "GND_A12_B1") (pintype "power_in"))
      (node (ref "J1") (pin "A1_B12") (pinfunction "GND_A1_B12") (pintype "power_in"))
      (node (ref "J2") (pin "1") (pinfunction "1_1") (pintype "passive"))
      (node (ref "J5") (pin "1") (pinfunction "1_1") (pintype "passive"))
      (node (ref "LED1") (pin "2") (pinfunction "K_2") (pintype "passive"))
      (node (ref "LED2") (pin "1") (pinfunction "K_1") (pintype "passive"))
      (node (ref "Q2") (pin "2") (pinfunction "S_2") (pintype "passive"))
      (node (ref "Q3") (pin "2") (pinfunction "E_2") (pintype "passive"))
      (node (ref "R1") (pin "2") (pinfunction "2_2") (pintype "passive"))
      (node (ref "R10") (pin "2") (pinfunction "2_2") (pintype "passive"))
      (node (ref "R18") (pin "1") (pinfunction "1_1") (pintype "passive"))
      (node (ref "R2") (pin "2") (pinfunction "2_2") (pintype "passive"))
      (node (ref "R29") (pin "1") (pinfunction "1_1") (pintype "passive"))
      (node (ref "R32") (pin "1") (pinfunction "1_1") (pintype "passive"))
      (node (ref "R4") (pin "1") (pinfunction "1_1") (pintype "passive"))
      (node (ref "R7") (pin "2") (pinfunction "2_2") (pintype "passive"))
      (node (ref "R9") (pin "2") (pinfunction "2_2") (pintype "passive"))
      (node (ref "RT1") (pin "1") (pinfunction "1_1") (pintype "passive"))
      (node (ref "S1") (pin "1") (pinfunction "COM_1") (pintype "passive"))
      (node (ref "S2") (pin "1") (pinfunction "COM_1") (pintype "passive"))
      (node (ref "U2") (pin "5") (pinfunction "GND_5") (pintype "passive"))
      (node (ref "U2") (pin "6") (pinfunction "SHELL_6") (pintype "passive"))
    )
    (net (code "31") (name "Midtap") (class "Default")
      (node (ref "J4") (pin "2") (pinfunction "2_2") (pintype "passive"))
      (node (ref "R17") (pin "1") (pinfunction "1_1") (pintype "passive"))
    )
    (net (code "32") (name "Net-(C7-Pad2)") (class "Default")
      (node (ref "C7") (pin "2") (pinfunction "2_2") (pintype "passive"))
      (node (ref "R7") (pin "1") (pinfunction "1_1") (pintype "passive"))
    )
    (net (code "33") (name "Net-(C10-Pad2)") (class "Default")
      (node (ref "C10") (pin "2") (pinfunction "2_2") (pintype "passive"))
      (node (ref "J1") (pin "SH1") (pinfunction "SHIELD_SH1") (pintype "passive"))
      (node (ref "J1") (pin "SH2") (pinfunction "SHIELD_SH2") (pintype "passive"))
      (node (ref "J1") (pin "SH3") (pinfunction "SHIELD_SH3") (pintype "passive"))
      (node (ref "J1") (pin "SH4") (pinfunction "SHIELD_SH4") (pintype "passive"))
      (node (ref "R4") (pin "2") (pinfunction "2_2") (pintype "passive"))
    )
    (net (code "34") (name "Net-(D1-K)") (class "Default")
      (node (ref "C1") (pin "1") (pinfunction "1_1") (pintype "passive"))
      (node (ref "D1") (pin "1") (pinfunction "K_1") (pintype "passive"))
      (node (ref "IC1") (pin "8") (pinfunction "PH_8") (pintype "passive"))
      (node (ref "L1") (pin "1") (pinfunction "1_1") (pintype "passive"))
    )
    (net (code "35") (name "Net-(IC1-BOOT)") (class "Default")
      (node (ref "C1") (pin "2") (pinfunction "2_2") (pintype "passive"))
      (node (ref "IC1") (pin "1") (pinfunction "BOOT_1") (pintype "passive"))
    )
    (net (code "36") (name "Net-(IC1-COMP)") (class "Default")
      (node (ref "C7") (pin "1") (pinfunction "1_1") (pintype "passive"))
      (node (ref "C8") (pin "1") (pinfunction "1_1") (pintype "passive"))
      (node (ref "IC1") (pin "6") (pinfunction "COMP_6") (pintype "passive"))
    )
    (net (code "37") (name "Net-(IC1-EN)") (class "Default")
      (node (ref "IC1") (pin "3") (pinfunction "EN_3") (pintype "passive"))
      (node (ref "R6") (pin "2") (pinfunction "2_2") (pintype "passive"))
      (node (ref "R9") (pin "1") (pinfunction "1_1") (pintype "passive"))
    )
    (net (code "38") (name "Net-(IC1-SS)") (class "Default")
      (node (ref "C9") (pin "1") (pinfunction "1_1") (pintype "passive"))
      (node (ref "IC1") (pin "4") (pinfunction "SS_4") (pintype "passive"))
    )
    (net (code "39") (name "Net-(IC1-VSENSE)") (class "Default")
      (node (ref "IC1") (pin "5") (pinfunction "VSENSE_5") (pintype "passive"))
      (node (ref "R10") (pin "1") (pinfunction "1_1") (pintype "passive"))
      (node (ref "R5") (pin "2") (pinfunction "2_2") (pintype "passive"))
    )
    (net (code "40") (name "Net-(IC2-EN)") (class "Default")
      (node (ref "C13") (pin "1") (pinfunction "1_1") (pintype "passive"))
      (node (ref "IC2") (pin "2") (pinfunction "EN_2") (pintype "passive"))
      (node (ref "R14") (pin "2") (pinfunction "2_2") (pintype "passive"))
      (node (ref "S1") (pin "2") (pinfunction "NO_2") (pintype "passive"))
    )
    (net (code "41") (name "Net-(IC3-GAIN_SLOT)") (class "Default")
      (node (ref "IC3") (pin "2") (pinfunction "GAIN_SLOT_2") (pintype "passive"))
      (node (ref "R23") (pin "2") (pinfunction "2_2") (pintype "passive"))
      (node (ref "R25") (pin "1") (pinfunction "1_1") (pintype "passive"))
    )
    (net (code "42") (name "Net-(IC3-~{SD_MODE})") (class "Default")
      (node (ref "IC3") (pin "4") (pinfunction "~{SD_MODE}_4") (pintype "passive"))
      (node (ref "R20") (pin "2") (pinfunction "2_2") (pintype "passive"))
    )
    (net (code "43") (name "Net-(IC4-BD_1)") (class "Default")
      (node (ref "C18") (pin "1") (pinfunction "1_1") (pintype "passive"))
      (node (ref "IC4") (pin "10") (pinfunction "BD_1_10") (pintype "passive"))
      (node (ref "IC4") (pin "13") (pinfunction "BD_2_13") (pintype "passive"))
    )
    (net (code "44") (name "Net-(IC4-BST)") (class "Default")
      (node (ref "C20") (pin "1") (pinfunction "1_1") (pintype "passive"))
      (node (ref "IC4") (pin "11") (pinfunction "BST_11") (pintype "passive"))
    )
    (net (code "45") (name "Net-(IC4-LX)") (class "Default")
      (node (ref "C20") (pin "2") (pinfunction "2_2") (pintype "passive"))
      (node (ref "IC4") (pin "14") (pinfunction "LX_14") (pintype "passive"))
      (node (ref "L2") (pin "1") (pinfunction "1_1") (pintype "passive"))
    )
    (net (code "46") (name "Net-(IC4-STAT)") (class "Default")
      (node (ref "IC4") (pin "1") (pinfunction "STAT_1") (pintype "passive"))
      (node (ref "LED3") (pin "2") (pinfunction "K_2") (pintype "passive"))
    )
    (net (code "47") (name "Net-(IC4-TIM)") (class "Default")
      (node (ref "C19") (pin "1") (pinfunction "1_1") (pintype "passive"))
      (node (ref "IC4") (pin "3") (pinfunction "TIM_3") (pintype "passive"))
    )
    (net (code "48") (name "Net-(LED1-A)") (class "Default")
      (node (ref "LED1") (pin "1") (pinfunction "A_1") (pintype "passive"))
      (node (ref "R8") (pin "1") (pinfunction "1_1") (pintype "passive"))
    )
    (net (code "49") (name "Net-(LED2-A)") (class "Default")
      (node (ref "LED2") (pin "2") (pinfunction "A_2") (pintype "passive"))
      (node (ref "R11") (pin "2") (pinfunction "2_2") (pintype "passive"))
    )
    (net (code "50") (name "Net-(LED3-A)") (class "Default")
      (node (ref "LED3") (pin "1") (pinfunction "A_1") (pintype "passive"))
      (node (ref "R30") (pin "1") (pinfunction "1_1") (pintype "passive"))
    )
    (net (code "51") (name "Net-(Q1-D)") (class "Default")
      (node (ref "Q1") (pin "3") (pinfunction "D_3") (pintype "passive"))
      (node (ref "Q2") (pin "3") (pinfunction "D_3") (pintype "passive"))
      (node (ref "R27") (pin "2") (pinfunction "2_2") (pintype "passive"))
    )
    (net (code "52") (name "Net-(Q1-G)") (class "Default")
      (node (ref "Q1") (pin "1") (pinfunction "G_1") (pintype "passive"))
      (node (ref "R21") (pin "1") (pinfunction "1_1") (pintype "passive"))
    )
    (net (code "53") (name "Net-(Q1-S)") (class "Default")
      (node (ref "Q1") (pin "2") (pinfunction "S_2") (pintype "passive"))
      (node (ref "R24") (pin "1") (pinfunction "1_1") (pintype "passive"))
      (node (ref "R26") (pin "2") (pinfunction "2_2") (pintype "passive"))
    )
    (net (code "54") (name "Net-(Q2-G)") (class "Default")
      (node (ref "Q2") (pin "1") (pinfunction "G_1") (pintype "passive"))
      (node (ref "R22") (pin "1") (pinfunction "1_1") (pintype "passive"))
    )
    (net (code "55") (name "Net-(Q3-B)") (class "Default")
      (node (ref "Q3") (pin "1") (pinfunction "B_1") (pintype "passive"))
      (node (ref "R34") (pin "2") (pinfunction "2_2") (pintype "passive"))
    )
    (net (code "56") (name "Net-(R3-Pad2)") (class "Default")
      (node (ref "R3") (pin "2") (pinfunction "2_2") (pintype "passive"))
      (node (ref "R5") (pin "1") (pinfunction "1_1") (pintype "passive"))
    )
    (net (code "57") (name "Net-(R29-Pad2)") (class "Default")
      (node (ref "R29") (pin "2") (pinfunction "2_2") (pintype "passive"))
      (node (ref "SW1") (pin "3") (pinfunction "3_3") (pintype "passive"))
    )
    (net (code "58") (name "Net-(R32-Pad2)") (class "Default")
      (node (ref "R32") (pin "2") (pinfunction "2_2") (pintype "passive"))
      (node (ref "SW1") (pin "1") (pinfunction "1_1") (pintype "passive"))
    )
    (net (code "59") (name "Net-(U1-CO)") (class "Default")
      (node (ref "R22") (pin "2") (pinfunction "2_2") (pintype "passive"))
      (node (ref "U1") (pin "9") (pinfunction "CO_9") (pintype "passive"))
    )
    (net (code "60") (name "Net-(U1-DO)") (class "Default")
      (node (ref "R21") (pin "2") (pinfunction "2_2") (pintype "passive"))
      (node (ref "U1") (pin "8") (pinfunction "DO_8") (pintype "passive"))
    )
    (net (code "61") (name "Net-(U1-RTS)") (class "Default")
      (node (ref "R19") (pin "1") (pinfunction "1_1") (pintype "passive"))
      (node (ref "RNTC1") (pin "2") (pinfunction "2_2") (pintype "passive"))
      (node (ref "U1") (pin "5") (pinfunction "RTS_5") (pintype "passive"))
    )
    (net (code "62") (name "Net-(U1-RTV)") (class "Default")
      (node (ref "R19") (pin "2") (pinfunction "2_2") (pintype "passive"))
      (node (ref "U1") (pin "6") (pinfunction "RTV_6") (pintype "passive"))
    )
    (net (code "63") (name "Net-(U1-VC1)") (class "Default")
      (node (ref "C16") (pin "1") (pinfunction "1_1") (pintype "passive"))
      (node (ref "R15") (pin "2") (pinfunction "2_2") (pintype "passive"))
      (node (ref "U1") (pin "1") (pinfunction "VC1_1") (pintype "passive"))
    )
    (net (code "64") (name "Net-(U1-VC2)") (class "Default")
      (node (ref "C17") (pin "1") (pinfunction "1_1") (pintype "passive"))
      (node (ref "R17") (pin "2") (pinfunction "2_2") (pintype "passive"))
      (node (ref "U1") (pin "2") (pinfunction "VC2_2") (pintype "passive"))
    )
    (net (code "65") (name "Net-(U1-VIN)") (class "Default")
      (node (ref "R24") (pin "2") (pinfunction "2_2") (pintype "passive"))
      (node (ref "U1") (pin "7") (pinfunction "VIN_7") (pintype "passive"))
    )
    (net (code "66") (name "Net-(U1-VM)") (class "Default")
      (node (ref "R18") (pin "2") (pinfunction "2_2") (pintype "passive"))
      (node (ref "U1") (pin "10") (pinfunction "VM_10") (pintype "passive"))
    )
    (net (code "67") (name "Vin_Buck") (class "Default")
      (node (ref "C4") (pin "1") (pinfunction "1_1") (pintype "passive"))
      (node (ref "C5") (pin "1") (pinfunction "1_1") (pintype "passive"))
      (node (ref "C6") (pin "1") (pinfunction "1_1") (pintype "passive"))
      (node (ref "IC1") (pin "2") (pinfunction "VIN_2") (pintype "passive"))
      (node (ref "J2") (pin "2") (pinfunction "2_2") (pintype "passive"))
      (node (ref "R11") (pin "1") (pinfunction "1_1") (pintype "passive"))
      (node (ref "R6") (pin "1") (pinfunction "1_1") (pintype "passive"))
      (node (ref "SW1") (pin "5") (pinfunction "5_5") (pintype "passive"))
    )
    (net (code "68") (name "unconnected-(B1-Pad4)") (class "Default")
      (node (ref "B1") (pin "4") (pinfunction "4_4") (pintype "passive+no_connect"))
    )
    (net (code "69") (name "unconnected-(B2-Pad4)") (class "Default")
      (node (ref "B2") (pin "4") (pinfunction "4_4") (pintype "passive+no_connect"))
    )
    (net (code "70") (name "unconnected-(B3-Pad4)") (class "Default")
      (node (ref "B3") (pin "4") (pinfunction "4_4") (pintype "passive+no_connect"))
    )
    (net (code "71") (name "unconnected-(B4-Pad4)") (class "Default")
      (node (ref "B4") (pin "4") (pinfunction "4_4") (pintype "passive+no_connect"))
    )
    (net (code "72") (name "unconnected-(IC3-N.C._1-Pad5)") (class "Default")
      (node (ref "IC3") (pin "5") (pinfunction "N.C._1_5") (pintype "passive+no_connect"))
    )
    (net (code "73") (name "unconnected-(IC3-N.C._2-Pad6)") (class "Default")
      (node (ref "IC3") (pin "6") (pinfunction "N.C._2_6") (pintype "passive+no_connect"))
    )
    (net (code "74") (name "unconnected-(IC3-N.C._3-Pad12)") (class "Default")
      (node (ref "IC3") (pin "12") (pinfunction "N.C._3_12") (pintype "passive+no_connect"))
    )
    (net (code "75") (name "unconnected-(IC3-N.C._4-Pad13)") (class "Default")
      (node (ref "IC3") (pin "13") (pinfunction "N.C._4_13") (pintype "passive+no_connect"))
    )
    (net (code "76") (name "unconnected-(IC4-ILIM-Pad6)") (class "Default")
      (node (ref "IC4") (pin "6") (pinfunction "ILIM_6") (pintype "passive+no_connect"))
    )
    (net (code "77") (name "unconnected-(IC4-SYSRT-Pad2)") (class "Default")
      (node (ref "IC4") (pin "2") (pinfunction "SYSRT_2") (pintype "passive+no_connect"))
    )
    (net (code "78") (name "unconnected-(J1-SBU1-PadA8)") (class "Default")
      (node (ref "J1") (pin "A8") (pinfunction "SBU1_A8") (pintype "bidirectional+no_connect"))
    )
    (net (code "79") (name "unconnected-(J1-SBU2-PadB8)") (class "Default")
      (node (ref "J1") (pin "B8") (pinfunction "SBU2_B8") (pintype "bidirectional+no_connect"))
    )
    (net (code "80") (name "unconnected-(SW2-Pad1)") (class "Default")
      (node (ref "SW2") (pin "1") (pinfunction "1_1") (pintype "passive"))
    )
    (net (code "81") (name "unconnected-(SW2-Pad6)") (class "Default")
      (node (ref "SW2") (pin "6") (pinfunction "6_6") (pintype "passive"))
    )
    (net (code "82") (name "unconnected-(U1-NC-Pad4)") (class "Default")
      (node (ref "U1") (pin "4") (pinfunction "NC_4") (pintype "passive+no_connect"))
    )
    (net (code "83") (name "unconnected-(U2-SWITCH-Pad4)") (class "Default")
      (node (ref "U2") (pin "4") (pinfunction "SWITCH_4") (pintype "passive+no_connect"))
    )
  )
)
